# NC1-2-Top.net
KiCad netlist of a schematic drawn in Altium Designer
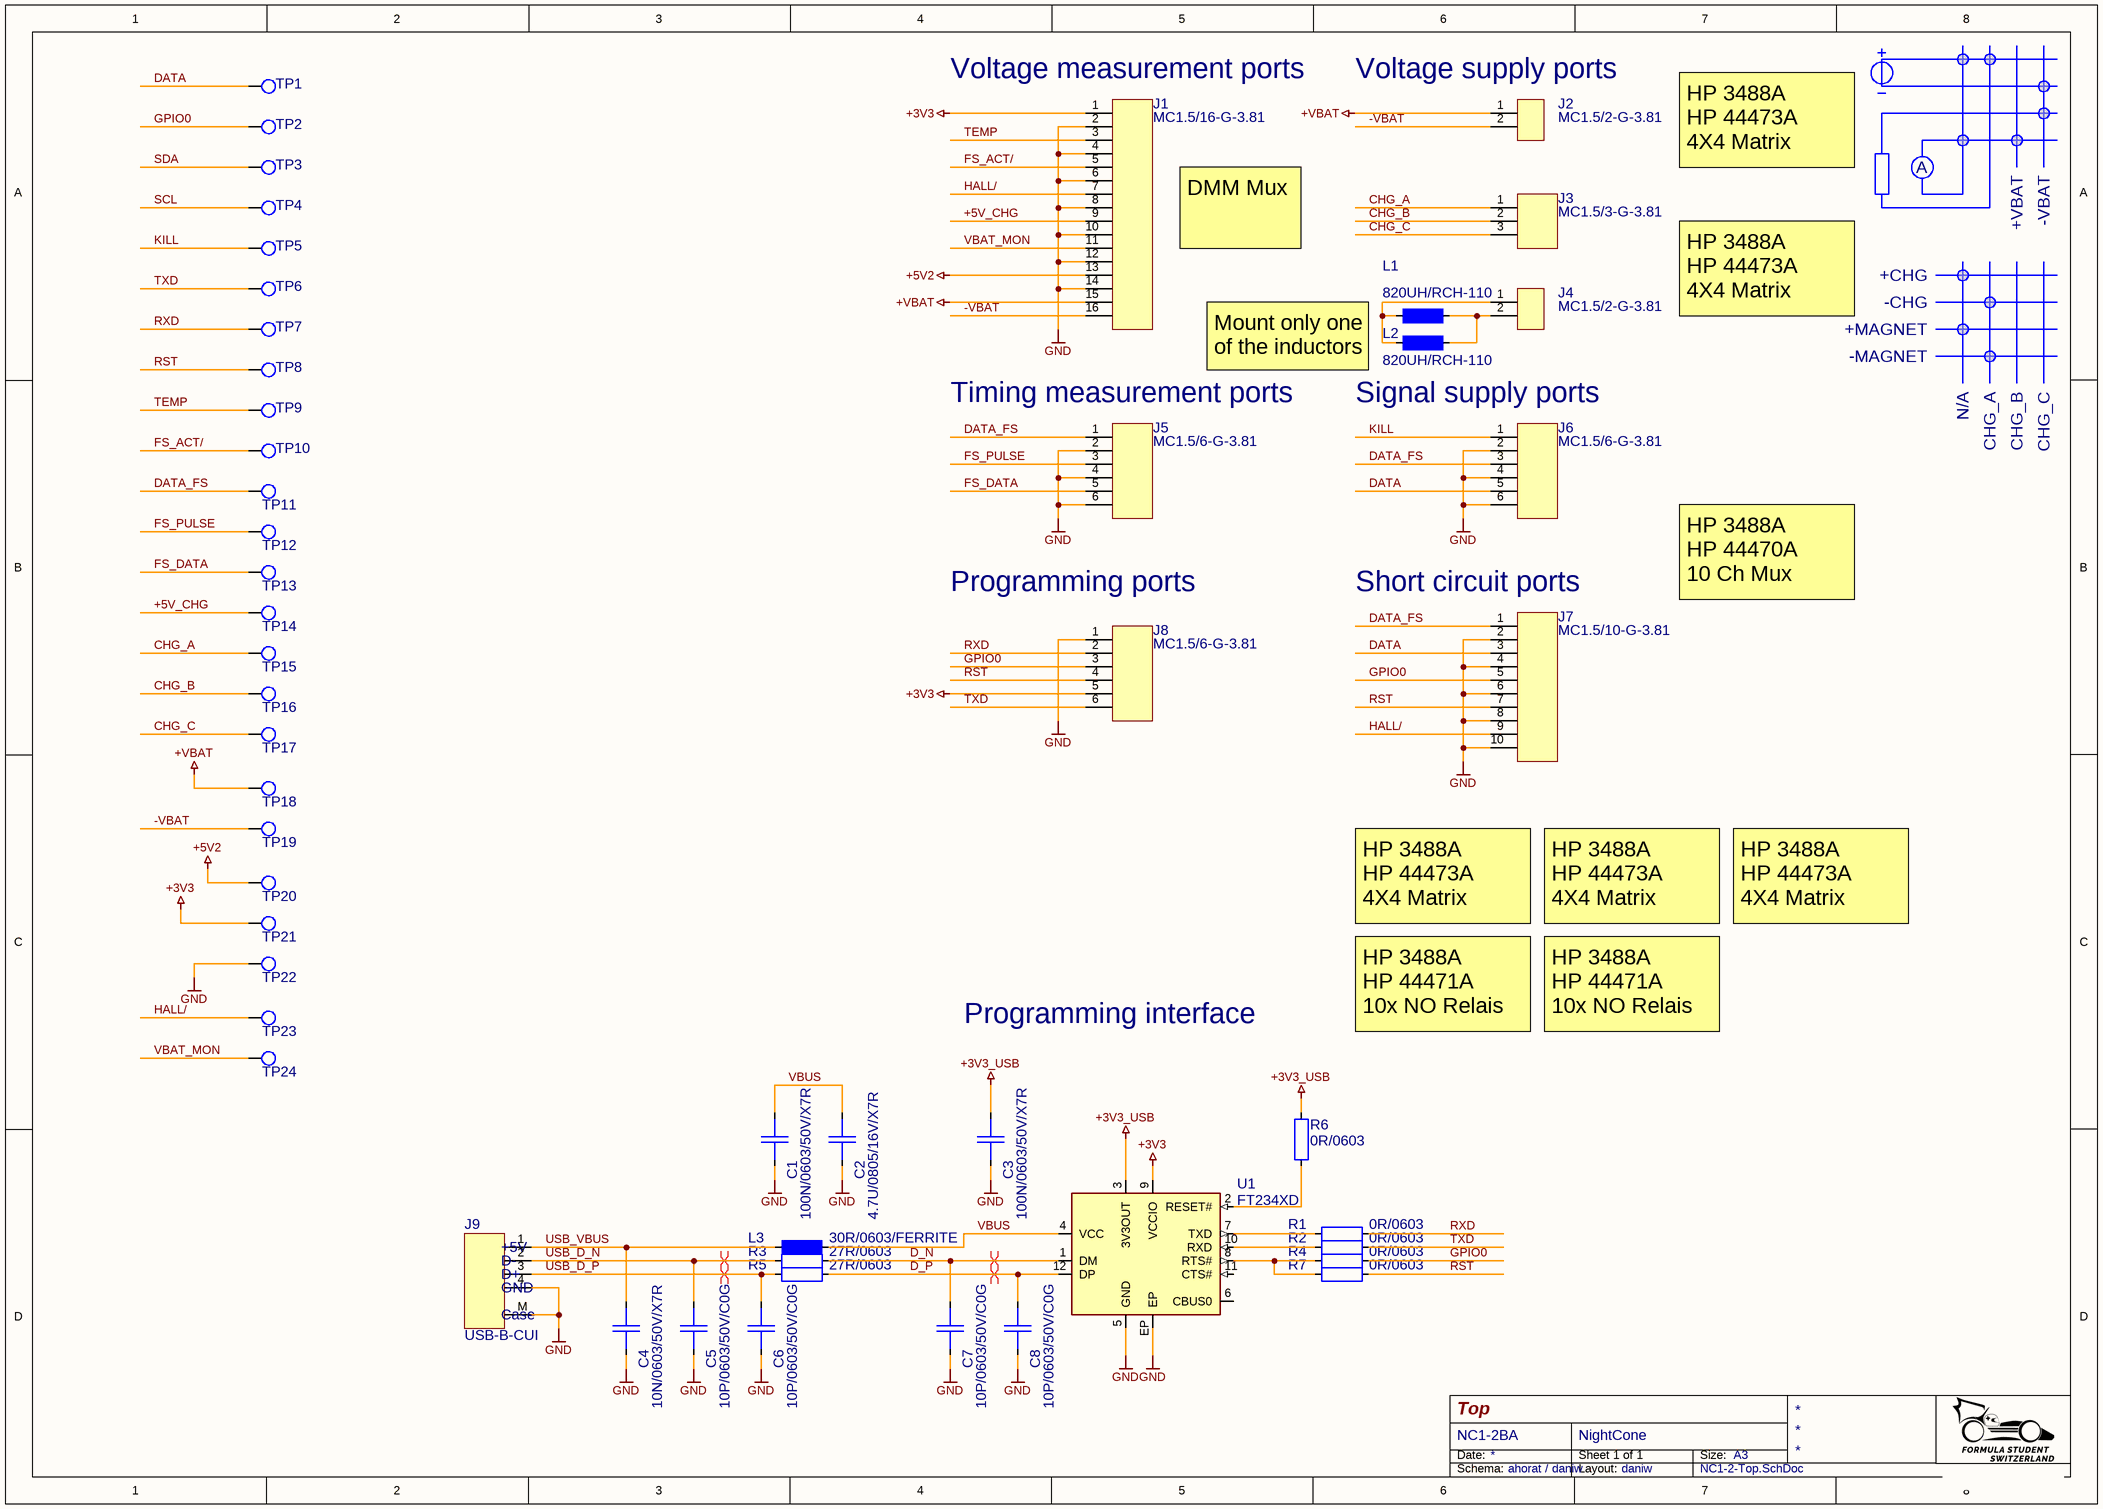
[diagram p0: NC1-2-Top.SchDoc]

(export (version "E")
  (design (tool "Eeschema 10.0.6"))
  (components
    (comp (ref "C1")
      (value "100N/0603/50V/X7R")
      (footprint "CAP0603_X7R")
      (description "CAP SM 0603 100nF 50V X7R")
      (fields (field (name "MANUFACTURER") "GENERIC"))
      (libsource (lib "daniw_altium_lib") (part "C"))
    )
    (comp (ref "C2")
      (value "4.7U/0805/16V/X7R")
      (footprint "CAP0805_X7R")
      (description "CAP SM 0805 4.7uF 16V X7R")
      (fields (field (name "MANUFACTURER") "GENERIC"))
      (libsource (lib "daniw_altium_lib") (part "C"))
    )
    (comp (ref "C3")
      (value "100N/0603/50V/X7R")
      (footprint "CAP0603_X7R")
      (description "CAP SM 0603 100nF 50V X7R")
      (fields (field (name "MANUFACTURER") "GENERIC"))
      (libsource (lib "daniw_altium_lib") (part "C"))
    )
    (comp (ref "C4")
      (value "10N/0603/50V/X7R")
      (footprint "CAP0603_X7R")
      (description "CAP SM 0603 10nF 50V X7R")
      (fields (field (name "MANUFACTURER") "GENERIC"))
      (libsource (lib "daniw_altium_lib") (part "C"))
    )
    (comp (ref "C5")
      (value "10P/0603/50V/C0G")
      (footprint "CAP0603_C0G")
      (description "CAP SM 0603 10pF 50V C0G")
      (fields (field (name "MANUFACTURER") "GENERIC"))
      (libsource (lib "daniw_altium_lib") (part "C"))
    )
    (comp (ref "C6")
      (value "10P/0603/50V/C0G")
      (footprint "CAP0603_C0G")
      (description "CAP SM 0603 10pF 50V C0G")
      (fields (field (name "MANUFACTURER") "GENERIC"))
      (libsource (lib "daniw_altium_lib") (part "C"))
    )
    (comp (ref "C7")
      (value "10P/0603/50V/C0G")
      (footprint "CAP0603_C0G")
      (description "CAP SM 0603 10pF 50V C0G")
      (fields (field (name "MANUFACTURER") "GENERIC"))
      (libsource (lib "daniw_altium_lib") (part "C"))
    )
    (comp (ref "C8")
      (value "10P/0603/50V/C0G")
      (footprint "CAP0603_C0G")
      (description "CAP SM 0603 10pF 50V C0G")
      (fields (field (name "MANUFACTURER") "GENERIC"))
      (libsource (lib "daniw_altium_lib") (part "C"))
    )
    (comp (ref "J1")
      (value "MC1.5/16-G-3.81")
      (footprint "MC1.5/16-G-3.81")
      (description "Phoenix contact MC 1,5/ 16-G-3,81")
      (fields (field (name "MANUFACTURER") "Phoenix"))
      (libsource (lib "daniw_altium_lib") (part "CON16"))
    )
    (comp (ref "J2")
      (value "MC1.5/2-G-3.81")
      (footprint "MC1.5/2-G-3.81")
      (description "Phoenix contact MC 1,5/ 2-G-3,81")
      (fields (field (name "MANUFACTURER") "Phoenix"))
      (libsource (lib "daniw_altium_lib") (part "CON2"))
    )
    (comp (ref "J3")
      (value "MC1.5/3-G-3.81")
      (footprint "MC1.5/3-G-3.81")
      (description "Phoenix contact MC 1,5/ 3-G-3,81")
      (fields (field (name "MANUFACTURER") "Phoenix"))
      (libsource (lib "daniw_altium_lib") (part "CON3"))
    )
    (comp (ref "J4")
      (value "MC1.5/2-G-3.81")
      (footprint "MC1.5/2-G-3.81")
      (description "Phoenix contact MC 1,5/ 2-G-3,81")
      (fields (field (name "MANUFACTURER") "Phoenix"))
      (libsource (lib "daniw_altium_lib") (part "CON2"))
    )
    (comp (ref "J5")
      (value "MC1.5/6-G-3.81")
      (footprint "MC1.5/6-G-3.81")
      (description "Phoenix contact MC 1,5/ 6-G-3,81")
      (fields (field (name "MANUFACTURER") "Phoenix"))
      (libsource (lib "daniw_altium_lib") (part "CON6"))
    )
    (comp (ref "J6")
      (value "MC1.5/6-G-3.81")
      (footprint "MC1.5/6-G-3.81")
      (description "Phoenix contact MC 1,5/ 6-G-3,81")
      (fields (field (name "MANUFACTURER") "Phoenix"))
      (libsource (lib "daniw_altium_lib") (part "CON6"))
    )
    (comp (ref "J7")
      (value "MC1.5/10-G-3.81")
      (footprint "MC1.5/10-G-3.81")
      (description "Phoenix contact MC 1,5/ 10-G-3,81")
      (fields (field (name "MANUFACTURER") "Phoenix"))
      (libsource (lib "daniw_altium_lib") (part "CON10"))
    )
    (comp (ref "J8")
      (value "MC1.5/6-G-3.81")
      (footprint "MC1.5/6-G-3.81")
      (description "Phoenix contact MC 1,5/ 6-G-3,81")
      (fields (field (name "MANUFACTURER") "Phoenix"))
      (libsource (lib "daniw_altium_lib") (part "CON6"))
    )
    (comp (ref "J9")
      (value "USB-B-CUI")
      (footprint "USB-B_CUI_UJ2-BH-TH")
      (description "USB-B CUI UJ2-BH-TH")
      (fields (field (name "MANUFACTURER") "CUI"))
      (libsource (lib "daniw_altium_lib") (part "CON4-M_USB"))
    )
    (comp (ref "L1")
      (value "820UH/RCH-110")
      (footprint "RCH-110-SINGLE")
      (description "820UH unshielded inductor THT RCH-110")
      (fields (field (name "MANUFACTURER") "Sumida"))
      (libsource (lib "daniw_altium_lib") (part "L"))
    )
    (comp (ref "L2")
      (value "820UH/RCH-110")
      (footprint "RCH-110-SINGLE")
      (description "820UH unshielded inductor THT RCH-110")
      (fields (field (name "MANUFACTURER") "Sumida"))
      (libsource (lib "daniw_altium_lib") (part "L"))
    )
    (comp (ref "L3")
      (value "30R/0603/FERRITE")
      (footprint "FB0603")
      (description "30R@100MHz 5A 0603 Ferrite")
      (fields (field (name "MANUFACTURER") "GENERIC"))
      (libsource (lib "daniw_altium_lib") (part "Ferrite"))
    )
    (comp (ref "R1")
      (value "0R/0603")
      (footprint "R0603-0.40-WW")
      (description "RES SM 0603 0R")
      (fields (field (name "MANUFACTURER") "GENERIC"))
      (libsource (lib "daniw_altium_lib") (part "R"))
    )
    (comp (ref "R2")
      (value "0R/0603")
      (footprint "R0603-0.40-WW")
      (description "RES SM 0603 0R")
      (fields (field (name "MANUFACTURER") "GENERIC"))
      (libsource (lib "daniw_altium_lib") (part "R"))
    )
    (comp (ref "R3")
      (value "27R/0603")
      (footprint "R0603-0.40-WW")
      (description "RES SM 0603 27R")
      (fields (field (name "MANUFACTURER") "GENERIC"))
      (libsource (lib "daniw_altium_lib") (part "R"))
    )
    (comp (ref "R4")
      (value "0R/0603")
      (footprint "R0603-0.40-WW")
      (description "RES SM 0603 0R")
      (fields (field (name "MANUFACTURER") "GENERIC"))
      (libsource (lib "daniw_altium_lib") (part "R"))
    )
    (comp (ref "R5")
      (value "27R/0603")
      (footprint "R0603-0.40-WW")
      (description "RES SM 0603 27R")
      (fields (field (name "MANUFACTURER") "GENERIC"))
      (libsource (lib "daniw_altium_lib") (part "R"))
    )
    (comp (ref "R6")
      (value "0R/0603")
      (footprint "R0603-0.40-WW")
      (description "RES SM 0603 0R")
      (fields (field (name "MANUFACTURER") "GENERIC"))
      (libsource (lib "daniw_altium_lib") (part "R"))
    )
    (comp (ref "R7")
      (value "0R/0603")
      (footprint "R0603-0.40-WW")
      (description "RES SM 0603 0R")
      (fields (field (name "MANUFACTURER") "GENERIC"))
      (libsource (lib "daniw_altium_lib") (part "R"))
    )
    (comp (ref "TP1")
      (value "SPRING-PROBE-SLEEVE-25")
      (footprint "TP_SPRING_PROBE_S25-512")
      (fields (field (name "MANUFACTURER") "Harwin"))
      (libsource (lib "daniw_altium_lib") (part "Testpoint"))
    )
    (comp (ref "TP2")
      (value "SPRING-PROBE-SLEEVE-25")
      (footprint "TP_SPRING_PROBE_S25-512")
      (fields (field (name "MANUFACTURER") "Harwin"))
      (libsource (lib "daniw_altium_lib") (part "Testpoint"))
    )
    (comp (ref "TP3")
      (value "SPRING-PROBE-SLEEVE-25")
      (footprint "TP_SPRING_PROBE_S25-512")
      (fields (field (name "MANUFACTURER") "Harwin"))
      (libsource (lib "daniw_altium_lib") (part "Testpoint"))
    )
    (comp (ref "TP4")
      (value "SPRING-PROBE-SLEEVE-25")
      (footprint "TP_SPRING_PROBE_S25-512")
      (fields (field (name "MANUFACTURER") "Harwin"))
      (libsource (lib "daniw_altium_lib") (part "Testpoint"))
    )
    (comp (ref "TP5")
      (value "SPRING-PROBE-SLEEVE-25")
      (footprint "TP_SPRING_PROBE_S25-512")
      (fields (field (name "MANUFACTURER") "Harwin"))
      (libsource (lib "daniw_altium_lib") (part "Testpoint"))
    )
    (comp (ref "TP6")
      (value "SPRING-PROBE-SLEEVE-25")
      (footprint "TP_SPRING_PROBE_S25-512")
      (fields (field (name "MANUFACTURER") "Harwin"))
      (libsource (lib "daniw_altium_lib") (part "Testpoint"))
    )
    (comp (ref "TP7")
      (value "SPRING-PROBE-SLEEVE-25")
      (footprint "TP_SPRING_PROBE_S25-512")
      (fields (field (name "MANUFACTURER") "Harwin"))
      (libsource (lib "daniw_altium_lib") (part "Testpoint"))
    )
    (comp (ref "TP8")
      (value "SPRING-PROBE-SLEEVE-25")
      (footprint "TP_SPRING_PROBE_S25-512")
      (fields (field (name "MANUFACTURER") "Harwin"))
      (libsource (lib "daniw_altium_lib") (part "Testpoint"))
    )
    (comp (ref "TP9")
      (value "SPRING-PROBE-SLEEVE-25")
      (footprint "TP_SPRING_PROBE_S25-512")
      (fields (field (name "MANUFACTURER") "Harwin"))
      (libsource (lib "daniw_altium_lib") (part "Testpoint"))
    )
    (comp (ref "TP10")
      (value "SPRING-PROBE-SLEEVE-25")
      (footprint "TP_SPRING_PROBE_S25-512")
      (fields (field (name "MANUFACTURER") "Harwin"))
      (libsource (lib "daniw_altium_lib") (part "Testpoint"))
    )
    (comp (ref "TP11")
      (value "SPRING-PROBE-SLEEVE-25")
      (footprint "TP_SPRING_PROBE_S25-512")
      (fields (field (name "MANUFACTURER") "Harwin"))
      (libsource (lib "daniw_altium_lib") (part "Testpoint"))
    )
    (comp (ref "TP12")
      (value "SPRING-PROBE-SLEEVE-25")
      (footprint "TP_SPRING_PROBE_S25-512")
      (fields (field (name "MANUFACTURER") "Harwin"))
      (libsource (lib "daniw_altium_lib") (part "Testpoint"))
    )
    (comp (ref "TP13")
      (value "SPRING-PROBE-SLEEVE-25")
      (footprint "TP_SPRING_PROBE_S25-512")
      (fields (field (name "MANUFACTURER") "Harwin"))
      (libsource (lib "daniw_altium_lib") (part "Testpoint"))
    )
    (comp (ref "TP14")
      (value "SPRING-PROBE-SLEEVE-25")
      (footprint "TP_SPRING_PROBE_S25-512")
      (fields (field (name "MANUFACTURER") "Harwin"))
      (libsource (lib "daniw_altium_lib") (part "Testpoint"))
    )
    (comp (ref "TP15")
      (value "SPRING-PROBE-SLEEVE-25")
      (footprint "TP_SPRING_PROBE_S25-512")
      (fields (field (name "MANUFACTURER") "Harwin"))
      (libsource (lib "daniw_altium_lib") (part "Testpoint"))
    )
    (comp (ref "TP16")
      (value "SPRING-PROBE-SLEEVE-25")
      (footprint "TP_SPRING_PROBE_S25-512")
      (fields (field (name "MANUFACTURER") "Harwin"))
      (libsource (lib "daniw_altium_lib") (part "Testpoint"))
    )
    (comp (ref "TP17")
      (value "SPRING-PROBE-SLEEVE-25")
      (footprint "TP_SPRING_PROBE_S25-512")
      (fields (field (name "MANUFACTURER") "Harwin"))
      (libsource (lib "daniw_altium_lib") (part "Testpoint"))
    )
    (comp (ref "TP18")
      (value "SPRING-PROBE-SLEEVE-25")
      (footprint "TP_SPRING_PROBE_S25-512")
      (fields (field (name "MANUFACTURER") "Harwin"))
      (libsource (lib "daniw_altium_lib") (part "Testpoint"))
    )
    (comp (ref "TP19")
      (value "SPRING-PROBE-SLEEVE-25")
      (footprint "TP_SPRING_PROBE_S25-512")
      (fields (field (name "MANUFACTURER") "Harwin"))
      (libsource (lib "daniw_altium_lib") (part "Testpoint"))
    )
    (comp (ref "TP20")
      (value "SPRING-PROBE-SLEEVE-25")
      (footprint "TP_SPRING_PROBE_S25-512")
      (fields (field (name "MANUFACTURER") "Harwin"))
      (libsource (lib "daniw_altium_lib") (part "Testpoint"))
    )
    (comp (ref "TP21")
      (value "SPRING-PROBE-SLEEVE-25")
      (footprint "TP_SPRING_PROBE_S25-512")
      (fields (field (name "MANUFACTURER") "Harwin"))
      (libsource (lib "daniw_altium_lib") (part "Testpoint"))
    )
    (comp (ref "TP22")
      (value "SPRING-PROBE-SLEEVE-25")
      (footprint "TP_SPRING_PROBE_S25-512")
      (fields (field (name "MANUFACTURER") "Harwin"))
      (libsource (lib "daniw_altium_lib") (part "Testpoint"))
    )
    (comp (ref "TP23")
      (value "SPRING-PROBE-SLEEVE-25")
      (footprint "TP_SPRING_PROBE_S25-512")
      (fields (field (name "MANUFACTURER") "Harwin"))
      (libsource (lib "daniw_altium_lib") (part "Testpoint"))
    )
    (comp (ref "TP24")
      (value "SPRING-PROBE-SLEEVE-25")
      (footprint "TP_SPRING_PROBE_S25-512")
      (fields (field (name "MANUFACTURER") "Harwin"))
      (libsource (lib "daniw_altium_lib") (part "Testpoint"))
    )
    (comp (ref "U1")
      (value "FT234XD")
      (footprint "DFN045P300X300X080-12-EP160X250")
      (description "FT234XD USB TO BASIC UART IC")
      (fields (field (name "MANUFACTURER") "FTDI"))
      (libsource (lib "daniw_altium_lib") (part "FT234XD"))
    )
  )
  (nets
    (net (code "1") (name "+3V3") (class "Default")
      (node (ref "J1") (pin "1") (pintype "passive"))
      (node (ref "J8") (pin "5") (pintype "passive"))
      (node (ref "TP21") (pin "1") (pinfunction "1_1") (pintype "passive"))
      (node (ref "U1") (pin "9") (pinfunction "VCCIO_9") (pintype "passive"))
    )
    (net (code "2") (name "+3V3_USB") (class "Default")
      (node (ref "C3") (pin "1") (pinfunction "1_1") (pintype "passive"))
      (node (ref "R6") (pin "1") (pinfunction "1_1") (pintype "passive"))
      (node (ref "U1") (pin "3") (pinfunction "3V3OUT_3") (pintype "passive"))
    )
    (net (code "3") (name "+5V2") (class "Default")
      (node (ref "J1") (pin "13") (pintype "passive"))
      (node (ref "TP20") (pin "1") (pinfunction "1_1") (pintype "passive"))
    )
    (net (code "4") (name "+VBAT") (class "Default")
      (node (ref "J1") (pin "15") (pintype "passive"))
      (node (ref "J2") (pin "1") (pintype "passive"))
      (node (ref "TP18") (pin "1") (pinfunction "1_1") (pintype "passive"))
    )
    (net (code "5") (name "/+5V_CHG") (class "Default")
      (node (ref "J1") (pin "9") (pintype "passive"))
      (node (ref "TP14") (pin "1") (pinfunction "1_1") (pintype "passive"))
    )
    (net (code "6") (name "/-VBAT") (class "Default")
      (node (ref "J1") (pin "16") (pintype "passive"))
      (node (ref "J2") (pin "2") (pintype "passive"))
      (node (ref "TP19") (pin "1") (pinfunction "1_1") (pintype "passive"))
    )
    (net (code "7") (name "/CHG_A") (class "Default")
      (node (ref "J3") (pin "1") (pintype "passive"))
      (node (ref "TP15") (pin "1") (pinfunction "1_1") (pintype "passive"))
    )
    (net (code "8") (name "/CHG_B") (class "Default")
      (node (ref "J3") (pin "2") (pintype "passive"))
      (node (ref "TP16") (pin "1") (pinfunction "1_1") (pintype "passive"))
    )
    (net (code "9") (name "/CHG_C") (class "Default")
      (node (ref "J3") (pin "3") (pintype "passive"))
      (node (ref "TP17") (pin "1") (pinfunction "1_1") (pintype "passive"))
    )
    (net (code "10") (name "/DATA") (class "Default")
      (node (ref "J6") (pin "5") (pintype "passive"))
      (node (ref "J7") (pin "3") (pintype "passive"))
      (node (ref "TP1") (pin "1") (pinfunction "1_1") (pintype "passive"))
    )
    (net (code "11") (name "/DATA_FS") (class "Default")
      (node (ref "J5") (pin "1") (pintype "passive"))
      (node (ref "J6") (pin "3") (pintype "passive"))
      (node (ref "J7") (pin "1") (pintype "passive"))
      (node (ref "TP11") (pin "1") (pinfunction "1_1") (pintype "passive"))
    )
    (net (code "12") (name "/D_N") (class "Default")
      (node (ref "C7") (pin "1") (pinfunction "1_1") (pintype "passive"))
      (node (ref "R3") (pin "2") (pinfunction "2_2") (pintype "passive"))
      (node (ref "U1") (pin "1") (pinfunction "DM_1") (pintype "bidirectional"))
    )
    (net (code "13") (name "/D_P") (class "Default")
      (node (ref "C8") (pin "1") (pinfunction "1_1") (pintype "passive"))
      (node (ref "R5") (pin "2") (pinfunction "2_2") (pintype "passive"))
      (node (ref "U1") (pin "12") (pinfunction "DP_12") (pintype "bidirectional"))
    )
    (net (code "14") (name "/FS_ACT{slash}") (class "Default")
      (node (ref "J1") (pin "5") (pintype "passive"))
      (node (ref "TP10") (pin "1") (pinfunction "1_1") (pintype "passive"))
    )
    (net (code "15") (name "/FS_DATA") (class "Default")
      (node (ref "J5") (pin "5") (pintype "passive"))
      (node (ref "TP13") (pin "1") (pinfunction "1_1") (pintype "passive"))
    )
    (net (code "16") (name "/FS_PULSE") (class "Default")
      (node (ref "J5") (pin "3") (pintype "passive"))
      (node (ref "TP12") (pin "1") (pinfunction "1_1") (pintype "passive"))
    )
    (net (code "17") (name "/GPIO0") (class "Default")
      (node (ref "J7") (pin "5") (pintype "passive"))
      (node (ref "J8") (pin "3") (pintype "passive"))
      (node (ref "R4") (pin "2") (pinfunction "2_2") (pintype "passive"))
      (node (ref "TP2") (pin "1") (pinfunction "1_1") (pintype "passive"))
    )
    (net (code "18") (name "/HALL{slash}") (class "Default")
      (node (ref "J1") (pin "7") (pintype "passive"))
      (node (ref "J7") (pin "9") (pintype "passive"))
      (node (ref "TP23") (pin "1") (pinfunction "1_1") (pintype "passive"))
    )
    (net (code "19") (name "/KILL") (class "Default")
      (node (ref "J6") (pin "1") (pintype "passive"))
      (node (ref "TP5") (pin "1") (pinfunction "1_1") (pintype "passive"))
    )
    (net (code "20") (name "/RST") (class "Default")
      (node (ref "J7") (pin "7") (pintype "passive"))
      (node (ref "J8") (pin "4") (pintype "passive"))
      (node (ref "R7") (pin "2") (pinfunction "2_2") (pintype "passive"))
      (node (ref "TP8") (pin "1") (pinfunction "1_1") (pintype "passive"))
    )
    (net (code "21") (name "/RXD") (class "Default")
      (node (ref "J8") (pin "2") (pintype "passive"))
      (node (ref "R1") (pin "2") (pinfunction "2_2") (pintype "passive"))
      (node (ref "TP7") (pin "1") (pinfunction "1_1") (pintype "passive"))
    )
    (net (code "22") (name "/SCL") (class "Default")
      (node (ref "TP4") (pin "1") (pinfunction "1_1") (pintype "passive"))
    )
    (net (code "23") (name "/SDA") (class "Default")
      (node (ref "TP3") (pin "1") (pinfunction "1_1") (pintype "passive"))
    )
    (net (code "24") (name "/TEMP") (class "Default")
      (node (ref "J1") (pin "3") (pintype "passive"))
      (node (ref "TP9") (pin "1") (pinfunction "1_1") (pintype "passive"))
    )
    (net (code "25") (name "/TXD") (class "Default")
      (node (ref "J8") (pin "6") (pintype "passive"))
      (node (ref "R2") (pin "2") (pinfunction "2_2") (pintype "passive"))
      (node (ref "TP6") (pin "1") (pinfunction "1_1") (pintype "passive"))
    )
    (net (code "26") (name "/USB_D_N") (class "Default")
      (node (ref "C5") (pin "1") (pinfunction "1_1") (pintype "passive"))
      (node (ref "J9") (pin "2") (pintype "passive"))
      (node (ref "R3") (pin "1") (pinfunction "1_1") (pintype "passive"))
    )
    (net (code "27") (name "/USB_D_P") (class "Default")
      (node (ref "C6") (pin "1") (pinfunction "1_1") (pintype "passive"))
      (node (ref "J9") (pin "3") (pintype "passive"))
      (node (ref "R5") (pin "1") (pinfunction "1_1") (pintype "passive"))
    )
    (net (code "28") (name "/USB_VBUS") (class "Default")
      (node (ref "C4") (pin "1") (pinfunction "1_1") (pintype "passive"))
      (node (ref "J9") (pin "1") (pintype "passive"))
      (node (ref "L3") (pin "1") (pinfunction "1_1") (pintype "passive"))
    )
    (net (code "29") (name "/VBAT_MON") (class "Default")
      (node (ref "J1") (pin "11") (pintype "passive"))
      (node (ref "TP24") (pin "1") (pinfunction "1_1") (pintype "passive"))
    )
    (net (code "30") (name "/VBUS") (class "Default")
      (node (ref "C1") (pin "1") (pinfunction "1_1") (pintype "passive"))
      (node (ref "C2") (pin "1") (pinfunction "1_1") (pintype "passive"))
      (node (ref "L3") (pin "2") (pinfunction "2_2") (pintype "passive"))
      (node (ref "U1") (pin "4") (pinfunction "VCC_4") (pintype "passive"))
    )
    (net (code "31") (name "GND") (class "Default")
      (node (ref "C1") (pin "2") (pinfunction "2_2") (pintype "passive"))
      (node (ref "C2") (pin "2") (pinfunction "2_2") (pintype "passive"))
      (node (ref "C3") (pin "2") (pinfunction "2_2") (pintype "passive"))
      (node (ref "C4") (pin "2") (pinfunction "2_2") (pintype "passive"))
      (node (ref "C5") (pin "2") (pinfunction "2_2") (pintype "passive"))
      (node (ref "C6") (pin "2") (pinfunction "2_2") (pintype "passive"))
      (node (ref "C7") (pin "2") (pinfunction "2_2") (pintype "passive"))
      (node (ref "C8") (pin "2") (pinfunction "2_2") (pintype "passive"))
      (node (ref "J1") (pin "10") (pintype "passive"))
      (node (ref "J1") (pin "12") (pintype "passive"))
      (node (ref "J1") (pin "14") (pintype "passive"))
      (node (ref "J1") (pin "2") (pintype "passive"))
      (node (ref "J1") (pin "4") (pintype "passive"))
      (node (ref "J1") (pin "6") (pintype "passive"))
      (node (ref "J1") (pin "8") (pintype "passive"))
      (node (ref "J5") (pin "2") (pintype "passive"))
      (node (ref "J5") (pin "4") (pintype "passive"))
      (node (ref "J5") (pin "6") (pintype "passive"))
      (node (ref "J6") (pin "2") (pintype "passive"))
      (node (ref "J6") (pin "4") (pintype "passive"))
      (node (ref "J6") (pin "6") (pintype "passive"))
      (node (ref "J7") (pin "10") (pintype "passive"))
      (node (ref "J7") (pin "2") (pintype "passive"))
      (node (ref "J7") (pin "4") (pintype "passive"))
      (node (ref "J7") (pin "6") (pintype "passive"))
      (node (ref "J7") (pin "8") (pintype "passive"))
      (node (ref "J8") (pin "1") (pintype "passive"))
      (node (ref "J9") (pin "4") (pintype "passive"))
      (node (ref "J9") (pin "M") (pintype "passive"))
      (node (ref "TP22") (pin "1") (pinfunction "1_1") (pintype "passive"))
      (node (ref "U1") (pin "5") (pinfunction "GND_5") (pintype "passive"))
      (node (ref "U1") (pin "EP") (pinfunction "EP_EP") (pintype "passive"))
    )
    (net (code "32") (name "Net-(J4-Pad1)") (class "Default")
      (node (ref "J4") (pin "1") (pintype "passive"))
      (node (ref "L1") (pin "1") (pinfunction "1_1") (pintype "passive"))
      (node (ref "L2") (pin "1") (pinfunction "1_1") (pintype "passive"))
    )
    (net (code "33") (name "Net-(J4-Pad2)") (class "Default")
      (node (ref "J4") (pin "2") (pintype "passive"))
      (node (ref "L1") (pin "2") (pinfunction "2_2") (pintype "passive"))
      (node (ref "L2") (pin "2") (pinfunction "2_2") (pintype "passive"))
    )
    (net (code "34") (name "Net-(U1-RESET#)") (class "Default")
      (node (ref "R6") (pin "2") (pinfunction "2_2") (pintype "passive"))
      (node (ref "U1") (pin "2") (pinfunction "RESET#_2") (pintype "input"))
    )
    (net (code "35") (name "Net-(U1-RTS#)") (class "Default")
      (node (ref "R4") (pin "1") (pinfunction "1_1") (pintype "passive"))
      (node (ref "R7") (pin "1") (pinfunction "1_1") (pintype "passive"))
      (node (ref "U1") (pin "8") (pinfunction "RTS#_8") (pintype "output"))
    )
    (net (code "36") (name "Net-(U1-RXD)") (class "Default")
      (node (ref "R2") (pin "1") (pinfunction "1_1") (pintype "passive"))
      (node (ref "U1") (pin "10") (pinfunction "RXD_10") (pintype "input"))
    )
    (net (code "37") (name "Net-(U1-TXD)") (class "Default")
      (node (ref "R1") (pin "1") (pinfunction "1_1") (pintype "passive"))
      (node (ref "U1") (pin "7") (pinfunction "TXD_7") (pintype "output"))
    )
    (net (code "38") (name "unconnected-(U1-CBUS0-Pad6)") (class "Default")
      (node (ref "U1") (pin "6") (pinfunction "CBUS0_6") (pintype "bidirectional"))
    )
    (net (code "39") (name "unconnected-(U1-CTS#-Pad11)") (class "Default")
      (node (ref "U1") (pin "11") (pinfunction "CTS#_11") (pintype "input"))
    )
  )
)
